# ihm_shield.net
KiCad netlist of a schematic drawn in EAGLE
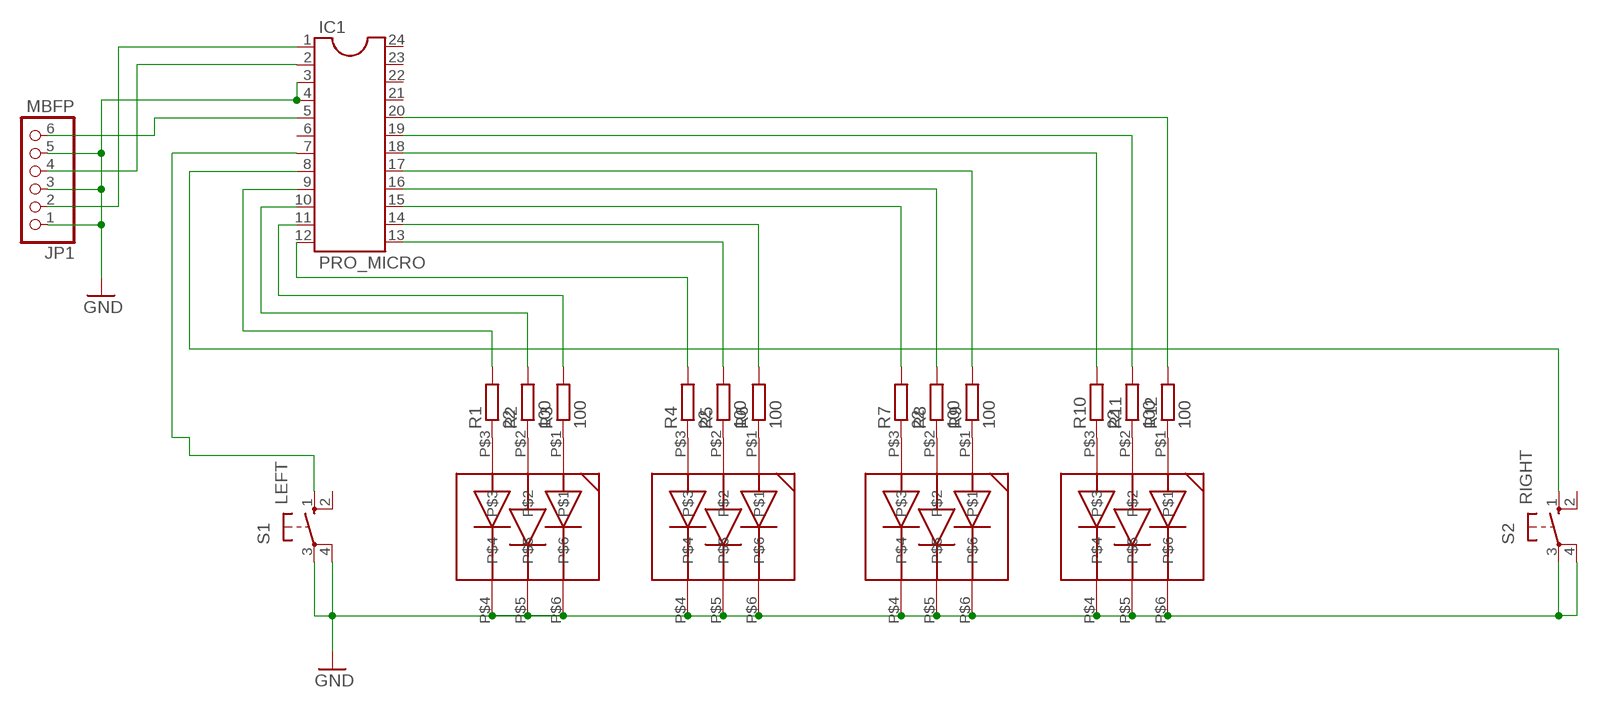
[diagram p0: schematic, sheet 1]

(export (version "E")
  (design (tool "Eeschema 10.0.6"))
  (components
    (comp (ref "IC1")
      (value "PRO_MICRO")
      (footprint "eagle-import:DIL24-6")
      (libsource (lib "eagle-import") (part "DIL24-6"))
    )
    (comp (ref "JP1")
      (value "MBFP")
      (footprint "eagle-import:1X06_90")
      (libsource (lib "eagle-import") (part "PINHD-1X6/90"))
    )
    (comp (ref "R1")
      (value "22")
      (footprint "eagle-import:R0805")
      (libsource (lib "eagle-import") (part "R-EU_R0805"))
    )
    (comp (ref "R2")
      (value "100")
      (footprint "eagle-import:R0805")
      (libsource (lib "eagle-import") (part "R-EU_R0805"))
    )
    (comp (ref "R3")
      (value "100")
      (footprint "eagle-import:R0805")
      (libsource (lib "eagle-import") (part "R-EU_R0805"))
    )
    (comp (ref "R4")
      (value "22")
      (footprint "eagle-import:R0805")
      (libsource (lib "eagle-import") (part "R-EU_R0805"))
    )
    (comp (ref "R5")
      (value "100")
      (footprint "eagle-import:R0805")
      (libsource (lib "eagle-import") (part "R-EU_R0805"))
    )
    (comp (ref "R6")
      (value "100")
      (footprint "eagle-import:R0805")
      (libsource (lib "eagle-import") (part "R-EU_R0805"))
    )
    (comp (ref "R7")
      (value "22")
      (footprint "eagle-import:R0805")
      (libsource (lib "eagle-import") (part "R-EU_R0805"))
    )
    (comp (ref "R8")
      (value "100")
      (footprint "eagle-import:R0805")
      (libsource (lib "eagle-import") (part "R-EU_R0805"))
    )
    (comp (ref "R9")
      (value "100")
      (footprint "eagle-import:R0805")
      (libsource (lib "eagle-import") (part "R-EU_R0805"))
    )
    (comp (ref "R10")
      (value "22")
      (footprint "eagle-import:R0805")
      (libsource (lib "eagle-import") (part "R-EU_R0805"))
    )
    (comp (ref "R11")
      (value "100")
      (footprint "eagle-import:R0805")
      (libsource (lib "eagle-import") (part "R-EU_R0805"))
    )
    (comp (ref "R12")
      (value "100")
      (footprint "eagle-import:R0805")
      (libsource (lib "eagle-import") (part "R-EU_R0805"))
    )
    (comp (ref "S1")
      (value "LEFT")
      (footprint "eagle-import:B3F-10XX")
      (fields (field (name "MPN") "B3F-1000"))
      (libsource (lib "eagle-import") (part "10-XX"))
    )
    (comp (ref "S2")
      (value "RIGHT")
      (footprint "eagle-import:B3F-10XX")
      (fields (field (name "MPN") "B3F-1000"))
      (libsource (lib "eagle-import") (part "10-XX"))
    )
    (comp (ref "U$1")
      (value "5050LED")
      (footprint "eagle-import:PLCC-6")
      (libsource (lib "eagle-import") (part "5050LED"))
    )
    (comp (ref "U$2")
      (value "5050LED")
      (footprint "eagle-import:PLCC-6")
      (libsource (lib "eagle-import") (part "5050LED"))
    )
    (comp (ref "U$3")
      (value "5050LED")
      (footprint "eagle-import:PLCC-6")
      (libsource (lib "eagle-import") (part "5050LED"))
    )
    (comp (ref "U$4")
      (value "5050LED")
      (footprint "eagle-import:PLCC-6")
      (libsource (lib "eagle-import") (part "5050LED"))
    )
  )
  (nets
    (net (code "1") (name "GND") (class "Default")
      (node (ref "IC1") (pin "3") (pinfunction "3_3") (pintype "passive"))
      (node (ref "IC1") (pin "4") (pinfunction "4_4") (pintype "passive"))
      (node (ref "JP1") (pin "1") (pinfunction "1_1") (pintype "passive"))
      (node (ref "JP1") (pin "3") (pinfunction "3_3") (pintype "passive"))
      (node (ref "JP1") (pin "5") (pinfunction "5_5") (pintype "passive"))
      (node (ref "S1") (pin "3") (pinfunction "P_3") (pintype "passive"))
      (node (ref "S1") (pin "4") (pinfunction "P1_4") (pintype "passive"))
      (node (ref "S2") (pin "3") (pinfunction "P_3") (pintype "passive"))
      (node (ref "S2") (pin "4") (pinfunction "P1_4") (pintype "passive"))
      (node (ref "U$1") (pin "P$4") (pinfunction "P$4_P$4") (pintype "bidirectional"))
      (node (ref "U$1") (pin "P$5") (pinfunction "P$5_P$5") (pintype "bidirectional"))
      (node (ref "U$1") (pin "P$6") (pinfunction "P$6_P$6") (pintype "bidirectional"))
      (node (ref "U$2") (pin "P$4") (pinfunction "P$4_P$4") (pintype "bidirectional"))
      (node (ref "U$2") (pin "P$5") (pinfunction "P$5_P$5") (pintype "bidirectional"))
      (node (ref "U$2") (pin "P$6") (pinfunction "P$6_P$6") (pintype "bidirectional"))
      (node (ref "U$3") (pin "P$4") (pinfunction "P$4_P$4") (pintype "bidirectional"))
      (node (ref "U$3") (pin "P$5") (pinfunction "P$5_P$5") (pintype "bidirectional"))
      (node (ref "U$3") (pin "P$6") (pinfunction "P$6_P$6") (pintype "bidirectional"))
      (node (ref "U$4") (pin "P$4") (pinfunction "P$4_P$4") (pintype "bidirectional"))
      (node (ref "U$4") (pin "P$5") (pinfunction "P$5_P$5") (pintype "bidirectional"))
      (node (ref "U$4") (pin "P$6") (pinfunction "P$6_P$6") (pintype "bidirectional"))
    )
    (net (code "2") (name "Net-(IC1-Pad1)") (class "Default")
      (node (ref "IC1") (pin "1") (pinfunction "1_1") (pintype "passive"))
      (node (ref "JP1") (pin "2") (pinfunction "2_2") (pintype "passive"))
    )
    (net (code "3") (name "Net-(IC1-Pad2)") (class "Default")
      (node (ref "IC1") (pin "2") (pinfunction "2_2") (pintype "passive"))
      (node (ref "JP1") (pin "4") (pinfunction "4_4") (pintype "passive"))
    )
    (net (code "4") (name "Net-(IC1-Pad5)") (class "Default")
      (node (ref "IC1") (pin "5") (pinfunction "5_5") (pintype "passive"))
      (node (ref "JP1") (pin "6") (pinfunction "6_6") (pintype "passive"))
    )
    (net (code "5") (name "Net-(IC1-Pad9)") (class "Default")
      (node (ref "IC1") (pin "9") (pinfunction "9_9") (pintype "passive"))
      (node (ref "R1") (pin "2") (pinfunction "2_2") (pintype "passive"))
    )
    (net (code "6") (name "Net-(IC1-Pad10)") (class "Default")
      (node (ref "IC1") (pin "10") (pinfunction "10_10") (pintype "passive"))
      (node (ref "R2") (pin "2") (pinfunction "2_2") (pintype "passive"))
    )
    (net (code "7") (name "Net-(IC1-Pad11)") (class "Default")
      (node (ref "IC1") (pin "11") (pinfunction "11_11") (pintype "passive"))
      (node (ref "R3") (pin "2") (pinfunction "2_2") (pintype "passive"))
    )
    (net (code "8") (name "Net-(IC1-Pad12)") (class "Default")
      (node (ref "IC1") (pin "12") (pinfunction "12_12") (pintype "passive"))
      (node (ref "R4") (pin "2") (pinfunction "2_2") (pintype "passive"))
    )
    (net (code "9") (name "Net-(IC1-Pad13)") (class "Default")
      (node (ref "IC1") (pin "13") (pinfunction "13_13") (pintype "passive"))
      (node (ref "R5") (pin "2") (pinfunction "2_2") (pintype "passive"))
    )
    (net (code "10") (name "Net-(IC1-Pad14)") (class "Default")
      (node (ref "IC1") (pin "14") (pinfunction "14_14") (pintype "passive"))
      (node (ref "R6") (pin "2") (pinfunction "2_2") (pintype "passive"))
    )
    (net (code "11") (name "Net-(IC1-Pad15)") (class "Default")
      (node (ref "IC1") (pin "15") (pinfunction "15_15") (pintype "passive"))
      (node (ref "R7") (pin "2") (pinfunction "2_2") (pintype "passive"))
    )
    (net (code "12") (name "Net-(IC1-Pad16)") (class "Default")
      (node (ref "IC1") (pin "16") (pinfunction "16_16") (pintype "passive"))
      (node (ref "R8") (pin "2") (pinfunction "2_2") (pintype "passive"))
    )
    (net (code "13") (name "Net-(IC1-Pad17)") (class "Default")
      (node (ref "IC1") (pin "17") (pinfunction "17_17") (pintype "passive"))
      (node (ref "R9") (pin "2") (pinfunction "2_2") (pintype "passive"))
    )
    (net (code "14") (name "Net-(IC1-Pad18)") (class "Default")
      (node (ref "IC1") (pin "18") (pinfunction "18_18") (pintype "passive"))
      (node (ref "R10") (pin "2") (pinfunction "2_2") (pintype "passive"))
    )
    (net (code "15") (name "Net-(IC1-Pad19)") (class "Default")
      (node (ref "IC1") (pin "19") (pinfunction "19_19") (pintype "passive"))
      (node (ref "R11") (pin "2") (pinfunction "2_2") (pintype "passive"))
    )
    (net (code "16") (name "Net-(IC1-Pad20)") (class "Default")
      (node (ref "IC1") (pin "20") (pinfunction "20_20") (pintype "passive"))
      (node (ref "R12") (pin "2") (pinfunction "2_2") (pintype "passive"))
    )
    (net (code "17") (name "Net-(R1-Pad1)") (class "Default")
      (node (ref "R1") (pin "1") (pinfunction "1_1") (pintype "passive"))
      (node (ref "U$1") (pin "P$3") (pinfunction "P$3_P$3") (pintype "bidirectional"))
    )
    (net (code "18") (name "Net-(R2-Pad1)") (class "Default")
      (node (ref "R2") (pin "1") (pinfunction "1_1") (pintype "passive"))
      (node (ref "U$1") (pin "P$2") (pinfunction "P$2_P$2") (pintype "bidirectional"))
    )
    (net (code "19") (name "Net-(R3-Pad1)") (class "Default")
      (node (ref "R3") (pin "1") (pinfunction "1_1") (pintype "passive"))
      (node (ref "U$1") (pin "P$1") (pinfunction "P$1_P$1") (pintype "bidirectional"))
    )
    (net (code "20") (name "Net-(R4-Pad1)") (class "Default")
      (node (ref "R4") (pin "1") (pinfunction "1_1") (pintype "passive"))
      (node (ref "U$2") (pin "P$3") (pinfunction "P$3_P$3") (pintype "bidirectional"))
    )
    (net (code "21") (name "Net-(R5-Pad1)") (class "Default")
      (node (ref "R5") (pin "1") (pinfunction "1_1") (pintype "passive"))
      (node (ref "U$2") (pin "P$2") (pinfunction "P$2_P$2") (pintype "bidirectional"))
    )
    (net (code "22") (name "Net-(R6-Pad1)") (class "Default")
      (node (ref "R6") (pin "1") (pinfunction "1_1") (pintype "passive"))
      (node (ref "U$2") (pin "P$1") (pinfunction "P$1_P$1") (pintype "bidirectional"))
    )
    (net (code "23") (name "Net-(R7-Pad1)") (class "Default")
      (node (ref "R7") (pin "1") (pinfunction "1_1") (pintype "passive"))
      (node (ref "U$3") (pin "P$3") (pinfunction "P$3_P$3") (pintype "bidirectional"))
    )
    (net (code "24") (name "Net-(R8-Pad1)") (class "Default")
      (node (ref "R8") (pin "1") (pinfunction "1_1") (pintype "passive"))
      (node (ref "U$3") (pin "P$2") (pinfunction "P$2_P$2") (pintype "bidirectional"))
    )
    (net (code "25") (name "Net-(R9-Pad1)") (class "Default")
      (node (ref "R9") (pin "1") (pinfunction "1_1") (pintype "passive"))
      (node (ref "U$3") (pin "P$1") (pinfunction "P$1_P$1") (pintype "bidirectional"))
    )
    (net (code "26") (name "Net-(R10-Pad1)") (class "Default")
      (node (ref "R10") (pin "1") (pinfunction "1_1") (pintype "passive"))
      (node (ref "U$4") (pin "P$3") (pinfunction "P$3_P$3") (pintype "bidirectional"))
    )
    (net (code "27") (name "Net-(R11-Pad1)") (class "Default")
      (node (ref "R11") (pin "1") (pinfunction "1_1") (pintype "passive"))
      (node (ref "U$4") (pin "P$2") (pinfunction "P$2_P$2") (pintype "bidirectional"))
    )
    (net (code "28") (name "Net-(R12-Pad1)") (class "Default")
      (node (ref "R12") (pin "1") (pinfunction "1_1") (pintype "passive"))
      (node (ref "U$4") (pin "P$1") (pinfunction "P$1_P$1") (pintype "bidirectional"))
    )
    (net (code "29") (name "Net-(S1-S)") (class "Default")
      (node (ref "IC1") (pin "7") (pinfunction "7_7") (pintype "passive"))
      (node (ref "S1") (pin "1") (pinfunction "S_1") (pintype "passive"))
    )
    (net (code "30") (name "Net-(S2-S)") (class "Default")
      (node (ref "IC1") (pin "8") (pinfunction "8_8") (pintype "passive"))
      (node (ref "S2") (pin "1") (pinfunction "S_1") (pintype "passive"))
    )
    (net (code "31") (name "unconnected-(IC1-Pad6)") (class "Default")
      (node (ref "IC1") (pin "6") (pinfunction "6_6") (pintype "passive"))
    )
    (net (code "32") (name "unconnected-(IC1-Pad21)") (class "Default")
      (node (ref "IC1") (pin "21") (pinfunction "21_21") (pintype "passive"))
    )
    (net (code "33") (name "unconnected-(IC1-Pad22)") (class "Default")
      (node (ref "IC1") (pin "22") (pinfunction "22_22") (pintype "passive"))
    )
    (net (code "34") (name "unconnected-(IC1-Pad23)") (class "Default")
      (node (ref "IC1") (pin "23") (pinfunction "23_23") (pintype "passive"))
    )
    (net (code "35") (name "unconnected-(IC1-Pad24)") (class "Default")
      (node (ref "IC1") (pin "24") (pinfunction "24_24") (pintype "passive"))
    )
    (net (code "36") (name "unconnected-(S1-S1-Pad2)") (class "Default")
      (node (ref "S1") (pin "2") (pinfunction "S1_2") (pintype "passive"))
    )
    (net (code "37") (name "unconnected-(S2-S1-Pad2)") (class "Default")
      (node (ref "S2") (pin "2") (pinfunction "S1_2") (pintype "passive"))
    )
  )
)
